# subckt_adjustable_LDO.net
KiCad netlist of a schematic drawn in Altium Designer
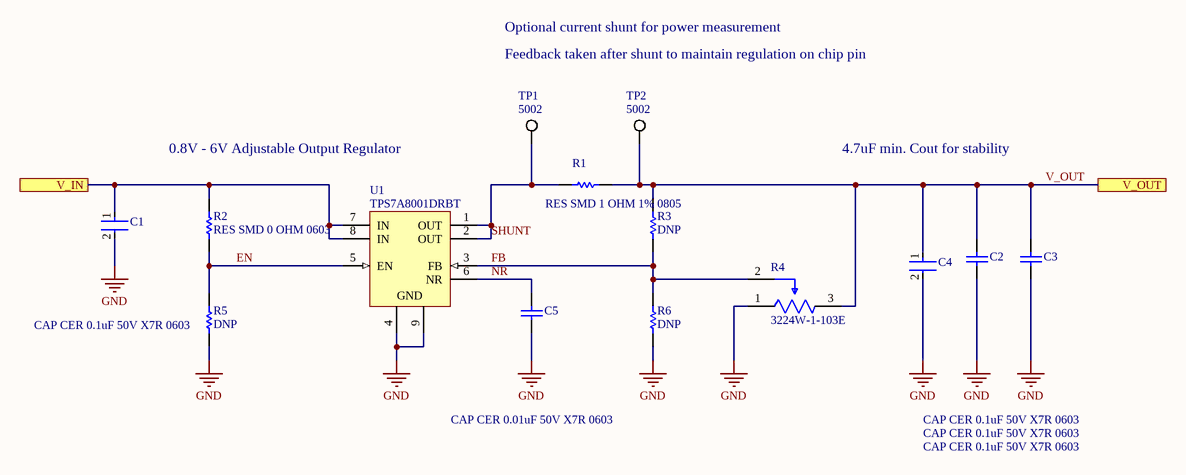
[diagram p0: subckt_adjustable_LDO.SchDoc]

(export (version "E")
  (design (tool "Eeschema 10.0.6"))
  (components
    (comp (ref "C1")
      (value "CAP CER 0.1uF 50V X7R 0603")
      (footprint "FP-CC0603-DA-MFG")
      (fields
        (field (name "OCTOPART") "https://octopart.com/cc0603krx7r7bb104-yageo-192941")
        (field (name "TOLERANCE") "0.1")
        (field (name "VOLTAGE") "16 V")
      )
      (libsource (lib "Altium Content Vault") (part "11868f565c42a9108669ba33697ecf6"))
    )
    (comp (ref "C2")
      (value "CAP CER 0.1uF 50V X7R 0603")
      (footprint "CAPC2013X140X50NL20T25")
      (fields
        (field (name "PART NUMBER") "0805ZC475KAT2A")
        (field (name "MANUFACTURER") "AVX Interconnect / Elco")
      )
      (libsource (lib "Altium Content Vault") (part "CAP"))
    )
    (comp (ref "C3")
      (value "CAP CER 0.1uF 50V X7R 0603")
      (footprint "CAPC2013X140X50NL20T25")
      (fields
        (field (name "PART NUMBER") "0805ZC475KAT2A")
        (field (name "MANUFACTURER") "AVX Interconnect / Elco")
      )
      (libsource (lib "Altium Content Vault") (part "CAP"))
    )
    (comp (ref "C4")
      (value "CAP CER 0.1uF 50V X7R 0603")
      (footprint "FP-CC0603-DA-MFG")
      (fields
        (field (name "OCTOPART") "https://octopart.com/cc0603krx7r7bb104-yageo-192941")
        (field (name "TOLERANCE") "0.1")
        (field (name "VOLTAGE") "16 V")
      )
      (libsource (lib "Altium Content Vault") (part "11868f565c42a9108669ba33697ecf6"))
    )
    (comp (ref "C5")
      (value "CAP CER 0.01uF 50V X7R 0603")
      (footprint "CAPC1608X90X40ML10T20")
      (fields
        (field (name "MANUFACTURER") "Yageo")
        (field (name "TOLERANCE") "10%")
        (field (name "VOLTAGE") "50V")
      )
      (libsource (lib "Altium Content Vault") (part "CAP-NP-2"))
    )
    (comp (ref "R1")
      (value "RES SMD 1 OHM 1% 0805")
      (footprint "RESC2013X50X30NL20T20")
      (fields (field (name "MANUFACTURER") "Vishay Dale") (field (name "PART NUMBER") "CRCW08050000Z0EB"))
      (libsource (lib "Altium Content Vault") (part "RES"))
    )
    (comp (ref "R2")
      (value "RES SMD 0 OHM 0603")
      (footprint "RESC1609X50X30LL10T20")
      (fields (field (name "PART NUMBER") "CRCW0603100KFKEA") (field (name "MANUFACTURER") "Vishay Dale"))
      (libsource (lib "Altium Content Vault") (part "RES"))
    )
    (comp (ref "R3")
      (value "DNP")
      (footprint "RESC1609X50X30LL10T20")
      (fields (field (name "PART NUMBER") "CRCW0603100KFKEA") (field (name "MANUFACTURER") "Vishay Dale"))
      (libsource (lib "Altium Content Vault") (part "RES"))
    )
    (comp (ref "R4")
      (value "3224W-1-103E")
      (footprint "FP-3224W-MFG")
      (description "TRIMMER 10K OHM 0.25W J LEAD TOP")
      (fields (field (name "TOLERANCE") "10%") (field (name "MANUFACTURER") "Bourns"))
      (libsource (lib "Altium Content Vault") (part "83d3d349ed884d1db45cec512f27eb6"))
    )
    (comp (ref "R5")
      (value "DNP")
      (footprint "RESC1609X50X30LL10T20")
      (fields (field (name "PART NUMBER") "CRCW0603100KFKEA") (field (name "MANUFACTURER") "Vishay Dale"))
      (libsource (lib "Altium Content Vault") (part "RES"))
    )
    (comp (ref "R6")
      (value "DNP")
      (footprint "RESC1609X50X30LL10T20")
      (fields (field (name "PART NUMBER") "CRCW0603100KFKEA") (field (name "MANUFACTURER") "Vishay Dale"))
      (libsource (lib "Altium Content Vault") (part "RES"))
    )
    (comp (ref "TP1")
      (value "5002")
      (footprint "KSTN-5002")
      (description "Test Point, White, 1-Pin THD, RoHS, Bulk")
      (fields (field (name "MANUFACTURER") "KeystoneElectronics"))
      (libsource (lib "Altium Content Vault") (part "KSTN-TP-5002"))
    )
    (comp (ref "TP2")
      (value "5002")
      (footprint "KSTN-5002")
      (description "Test Point, White, 1-Pin THD, RoHS, Bulk")
      (fields (field (name "MANUFACTURER") "KeystoneElectronics"))
      (libsource (lib "Altium Content Vault") (part "KSTN-TP-5002"))
    )
    (comp (ref "U1")
      (value "TPS7A8001DRBT")
      (footprint "DRB0008A_V")
      (fields (field (name "MANUFACTURER") "Texas Instruments"))
      (libsource (lib "Altium Content Vault") (part "TI-TPS7A8X01DRB8-1750X1500TP"))
    )
  )
  (nets
    (net (code "1") (name "/EN") (class "Default")
      (node (ref "R2") (pin "1") (pinfunction "1_1") (pintype "passive"))
      (node (ref "R5") (pin "2") (pinfunction "2_2") (pintype "passive"))
      (node (ref "U1") (pin "5") (pinfunction "EN_5") (pintype "input"))
    )
    (net (code "2") (name "/FB") (class "Default")
      (node (ref "R3") (pin "1") (pinfunction "1_1") (pintype "passive"))
      (node (ref "R4") (pin "2") (pinfunction "WIPER_2") (pintype "passive"))
      (node (ref "R6") (pin "2") (pinfunction "2_2") (pintype "passive"))
      (node (ref "U1") (pin "3") (pinfunction "FB_3") (pintype "input"))
    )
    (net (code "3") (name "/NR") (class "Default")
      (node (ref "C5") (pin "1") (pinfunction "1_1") (pintype "passive"))
      (node (ref "U1") (pin "6") (pinfunction "NR_6") (pintype "passive"))
    )
    (net (code "4") (name "/SHUNT") (class "Default")
      (node (ref "R1") (pin "1") (pinfunction "1_1") (pintype "passive"))
      (node (ref "TP1") (pin "1") (pintype "passive"))
      (node (ref "U1") (pin "1") (pinfunction "OUT_1") (pintype "power_in"))
      (node (ref "U1") (pin "2") (pinfunction "OUT_2") (pintype "power_in"))
    )
    (net (code "5") (name "/V_IN") (class "Default")
      (node (ref "C1") (pin "1") (pinfunction "1_1") (pintype "passive"))
      (node (ref "R2") (pin "2") (pinfunction "2_2") (pintype "passive"))
      (node (ref "U1") (pin "7") (pinfunction "IN_7") (pintype "power_in"))
      (node (ref "U1") (pin "8") (pinfunction "IN_8") (pintype "power_in"))
    )
    (net (code "6") (name "/V_OUT") (class "Default")
      (node (ref "C2") (pin "1") (pinfunction "1_1") (pintype "passive"))
      (node (ref "C3") (pin "1") (pinfunction "1_1") (pintype "passive"))
      (node (ref "C4") (pin "1") (pinfunction "1_1") (pintype "passive"))
      (node (ref "R1") (pin "2") (pinfunction "2_2") (pintype "passive"))
      (node (ref "R3") (pin "2") (pinfunction "2_2") (pintype "passive"))
      (node (ref "R4") (pin "3") (pinfunction "CW_3") (pintype "passive"))
      (node (ref "TP2") (pin "1") (pintype "passive"))
    )
    (net (code "7") (name "GND") (class "Default")
      (node (ref "C1") (pin "2") (pinfunction "2_2") (pintype "passive"))
      (node (ref "C2") (pin "2") (pinfunction "2_2") (pintype "passive"))
      (node (ref "C3") (pin "2") (pinfunction "2_2") (pintype "passive"))
      (node (ref "C4") (pin "2") (pinfunction "2_2") (pintype "passive"))
      (node (ref "C5") (pin "2") (pinfunction "2_2") (pintype "passive"))
      (node (ref "R4") (pin "1") (pinfunction "CCW_1") (pintype "passive"))
      (node (ref "R5") (pin "1") (pinfunction "1_1") (pintype "passive"))
      (node (ref "R6") (pin "1") (pinfunction "1_1") (pintype "passive"))
      (node (ref "U1") (pin "4") (pinfunction "GND_4") (pintype "power_in"))
      (node (ref "U1") (pin "9") (pinfunction "GND_9") (pintype "power_in"))
    )
  )
)
